# Sensor_current_100A.net
KiCad netlist of a schematic drawn in Altium Designer
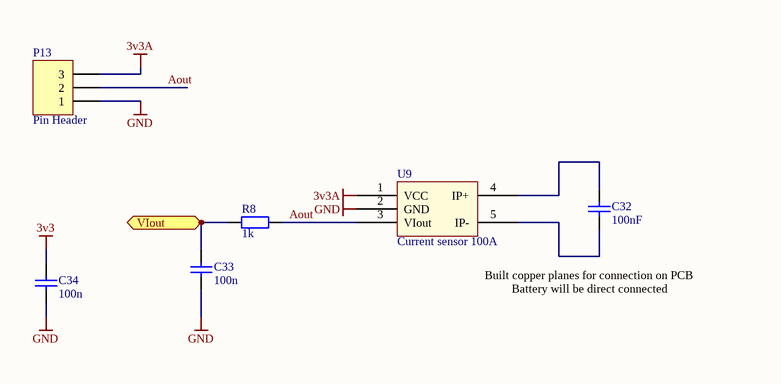
[diagram p0: Sensor current 100A.SchDoc]

(export (version "E")
  (design (tool "Eeschema 10.0.6"))
  (components
    (comp (ref "C32")
      (value "100nF")
      (footprint "C1206")
      (fields
        (field (name "PART NUMBER") "0.1uF")
        (field (name "VOLTAGE") "50V")
        (field (name "TOLERANCE") "0.1")
        (field (name "AUTHOR") "Willem Pietersz")
      )
      (libsource (lib "OurDb") (part "cap_NonPolar"))
    )
    (comp (ref "C33")
      (value "100n")
      (footprint "C0805")
      (fields (field (name "TOLERANCE") "0.1") (field (name "AUTHOR") "Willy Pietersz"))
      (libsource (lib "OurDb") (part "cap_NonPolar"))
    )
    (comp (ref "C34")
      (value "100n")
      (footprint "C0805")
      (fields (field (name "TOLERANCE") "0.1") (field (name "AUTHOR") "Willy Pietersz"))
      (libsource (lib "OurDb") (part "cap_NonPolar"))
    )
    (comp (ref "P13")
      (value "Pin Header")
      (footprint "PH1x3_2.54")
      (description "Con1x3")
      (fields (field (name "PART NUMBER") "PH1x3") (field (name "AUTHOR") "Willy Pietersz"))
      (libsource (lib "OurDb") (part "Con1x3"))
    )
    (comp (ref "R8")
      (value "1k")
      (footprint "R0805")
      (description "Resistor")
      (fields
        (field (name "PART NUMBER") "1K")
        (field (name "POWER") "0.25W")
        (field (name "PUBLISHER") "Altium Limited")
        (field (name "AUTHOR") "Willy Pietersz")
      )
      (libsource (lib "OurDb") (part "RESISTOR"))
    )
    (comp (ref "U9")
      (value "Current sensor 100A")
      (footprint "unique-ACS758xCB")
      (description "Sensor, Current")
      (fields (field (name "PART NUMBER") "ACS758xCB"))
      (libsource (lib "OurDb") (part "ACS758xCB"))
    )
  )
  (nets
    (net (code "1") (name "/Aout") (class "Default")
      (node (ref "P13") (pin "2") (pinfunction "2_2") (pintype "passive"))
      (node (ref "R8") (pin "1") (pinfunction "1_1") (pintype "passive"))
      (node (ref "U9") (pin "3") (pinfunction "VIout_3") (pintype "passive"))
    )
    (net (code "2") (name "/VIout") (class "Default")
      (node (ref "C33") (pin "2") (pinfunction "2_2") (pintype "passive"))
      (node (ref "R8") (pin "2") (pinfunction "2_2") (pintype "passive"))
    )
    (net (code "3") (name "3v3") (class "Default")
      (node (ref "C34") (pin "2") (pinfunction "2_2") (pintype "passive"))
    )
    (net (code "4") (name "3v3A") (class "Default")
      (node (ref "P13") (pin "3") (pinfunction "3_3") (pintype "passive"))
      (node (ref "U9") (pin "1") (pinfunction "VCC_1") (pintype "passive"))
    )
    (net (code "5") (name "GND") (class "Default")
      (node (ref "C33") (pin "1") (pinfunction "1_1") (pintype "passive"))
      (node (ref "C34") (pin "1") (pinfunction "1_1") (pintype "passive"))
      (node (ref "P13") (pin "1") (pinfunction "1_1") (pintype "passive"))
      (node (ref "U9") (pin "2") (pinfunction "GND_2") (pintype "passive"))
    )
    (net (code "6") (name "Net-(U9-IP+)") (class "Default")
      (node (ref "C32") (pin "2") (pinfunction "2_2") (pintype "passive"))
      (node (ref "U9") (pin "4") (pinfunction "IP+_4") (pintype "passive"))
    )
    (net (code "7") (name "Net-(U9-IP-)") (class "Default")
      (node (ref "C32") (pin "1") (pinfunction "1_1") (pintype "passive"))
      (node (ref "U9") (pin "5") (pinfunction "IP-_5") (pintype "passive"))
    )
  )
)
